# TriggerMount.net
KiCad netlist of a schematic drawn in EAGLE
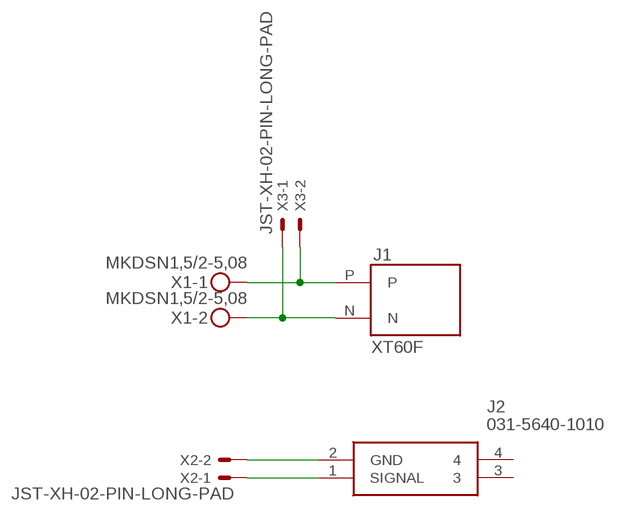
[diagram p0: schematic, sheet 1]

(export (version "E")
  (design (tool "Eeschema 10.0.6"))
  (components
    (comp (ref "J1")
      (value "XT60F")
      (footprint "eagle-import:XT60PW")
      (libsource (lib "eagle-import") (part "XT60F"))
    )
    (comp (ref "J2")
      (value "031-5640-1010")
      (footprint "eagle-import:03156401010")
      (fields (field (name "MOUSER_PART_NUMBER") "523-31-5640-1010"))
      (libsource (lib "eagle-import") (part "031-5640-1010"))
    )
    (comp (ref "X1")
      (value "MKDSN1,5/2-5,08")
      (footprint "eagle-import:MKDSN1,5_2-5,08")
      (libsource (lib "eagle-import") (part "MKDSN1,5/2-5,08"))
    )
    (comp (ref "X2")
      (value "JST-XH-02-PIN-LONG-PAD")
      (footprint "eagle-import:JST-XH-02-PACKAGE-LONG-PAD")
      (libsource (lib "eagle-import") (part "JST-XH-02-PIN-LONG-PAD"))
    )
    (comp (ref "X3")
      (value "JST-XH-02-PIN-LONG-PAD")
      (footprint "eagle-import:JST-XH-02-PACKAGE-LONG-PAD")
      (libsource (lib "eagle-import") (part "JST-XH-02-PIN-LONG-PAD"))
    )
  )
  (nets
    (net (code "1") (name "Net-(J2-GND)") (class "Default")
      (node (ref "J2") (pin "2") (pinfunction "GND_2") (pintype "bidirectional"))
      (node (ref "X2") (pin "2") (pinfunction "S_2") (pintype "passive"))
    )
    (net (code "2") (name "Net-(J2-SIGNAL)") (class "Default")
      (node (ref "J2") (pin "1") (pinfunction "SIGNAL_1") (pintype "bidirectional"))
      (node (ref "X2") (pin "1") (pinfunction "S_1") (pintype "passive"))
    )
    (net (code "3") (name "Net-(X1A-KL)") (class "Default")
      (node (ref "J1") (pin "P") (pinfunction "P_P") (pintype "bidirectional"))
      (node (ref "X1") (pin "1") (pinfunction "KL_1") (pintype "passive"))
      (node (ref "X3") (pin "2") (pinfunction "S_2") (pintype "passive"))
    )
    (net (code "4") (name "Net-(X1B-KL)") (class "Default")
      (node (ref "J1") (pin "N") (pinfunction "N_N") (pintype "bidirectional"))
      (node (ref "X1") (pin "2") (pinfunction "KL_2") (pintype "passive"))
      (node (ref "X3") (pin "1") (pinfunction "S_1") (pintype "passive"))
    )
    (net (code "5") (name "unconnected-(J2-Pad3)") (class "Default")
      (node (ref "J2") (pin "3") (pinfunction "3_3") (pintype "bidirectional"))
    )
    (net (code "6") (name "unconnected-(J2-Pad4)") (class "Default")
      (node (ref "J2") (pin "4") (pinfunction "4_4") (pintype "bidirectional"))
    )
  )
)
